# ProProject_MinSyBo_Star_2024-05-18.net
KiCad netlist of a schematic drawn in EasyEDA Pro
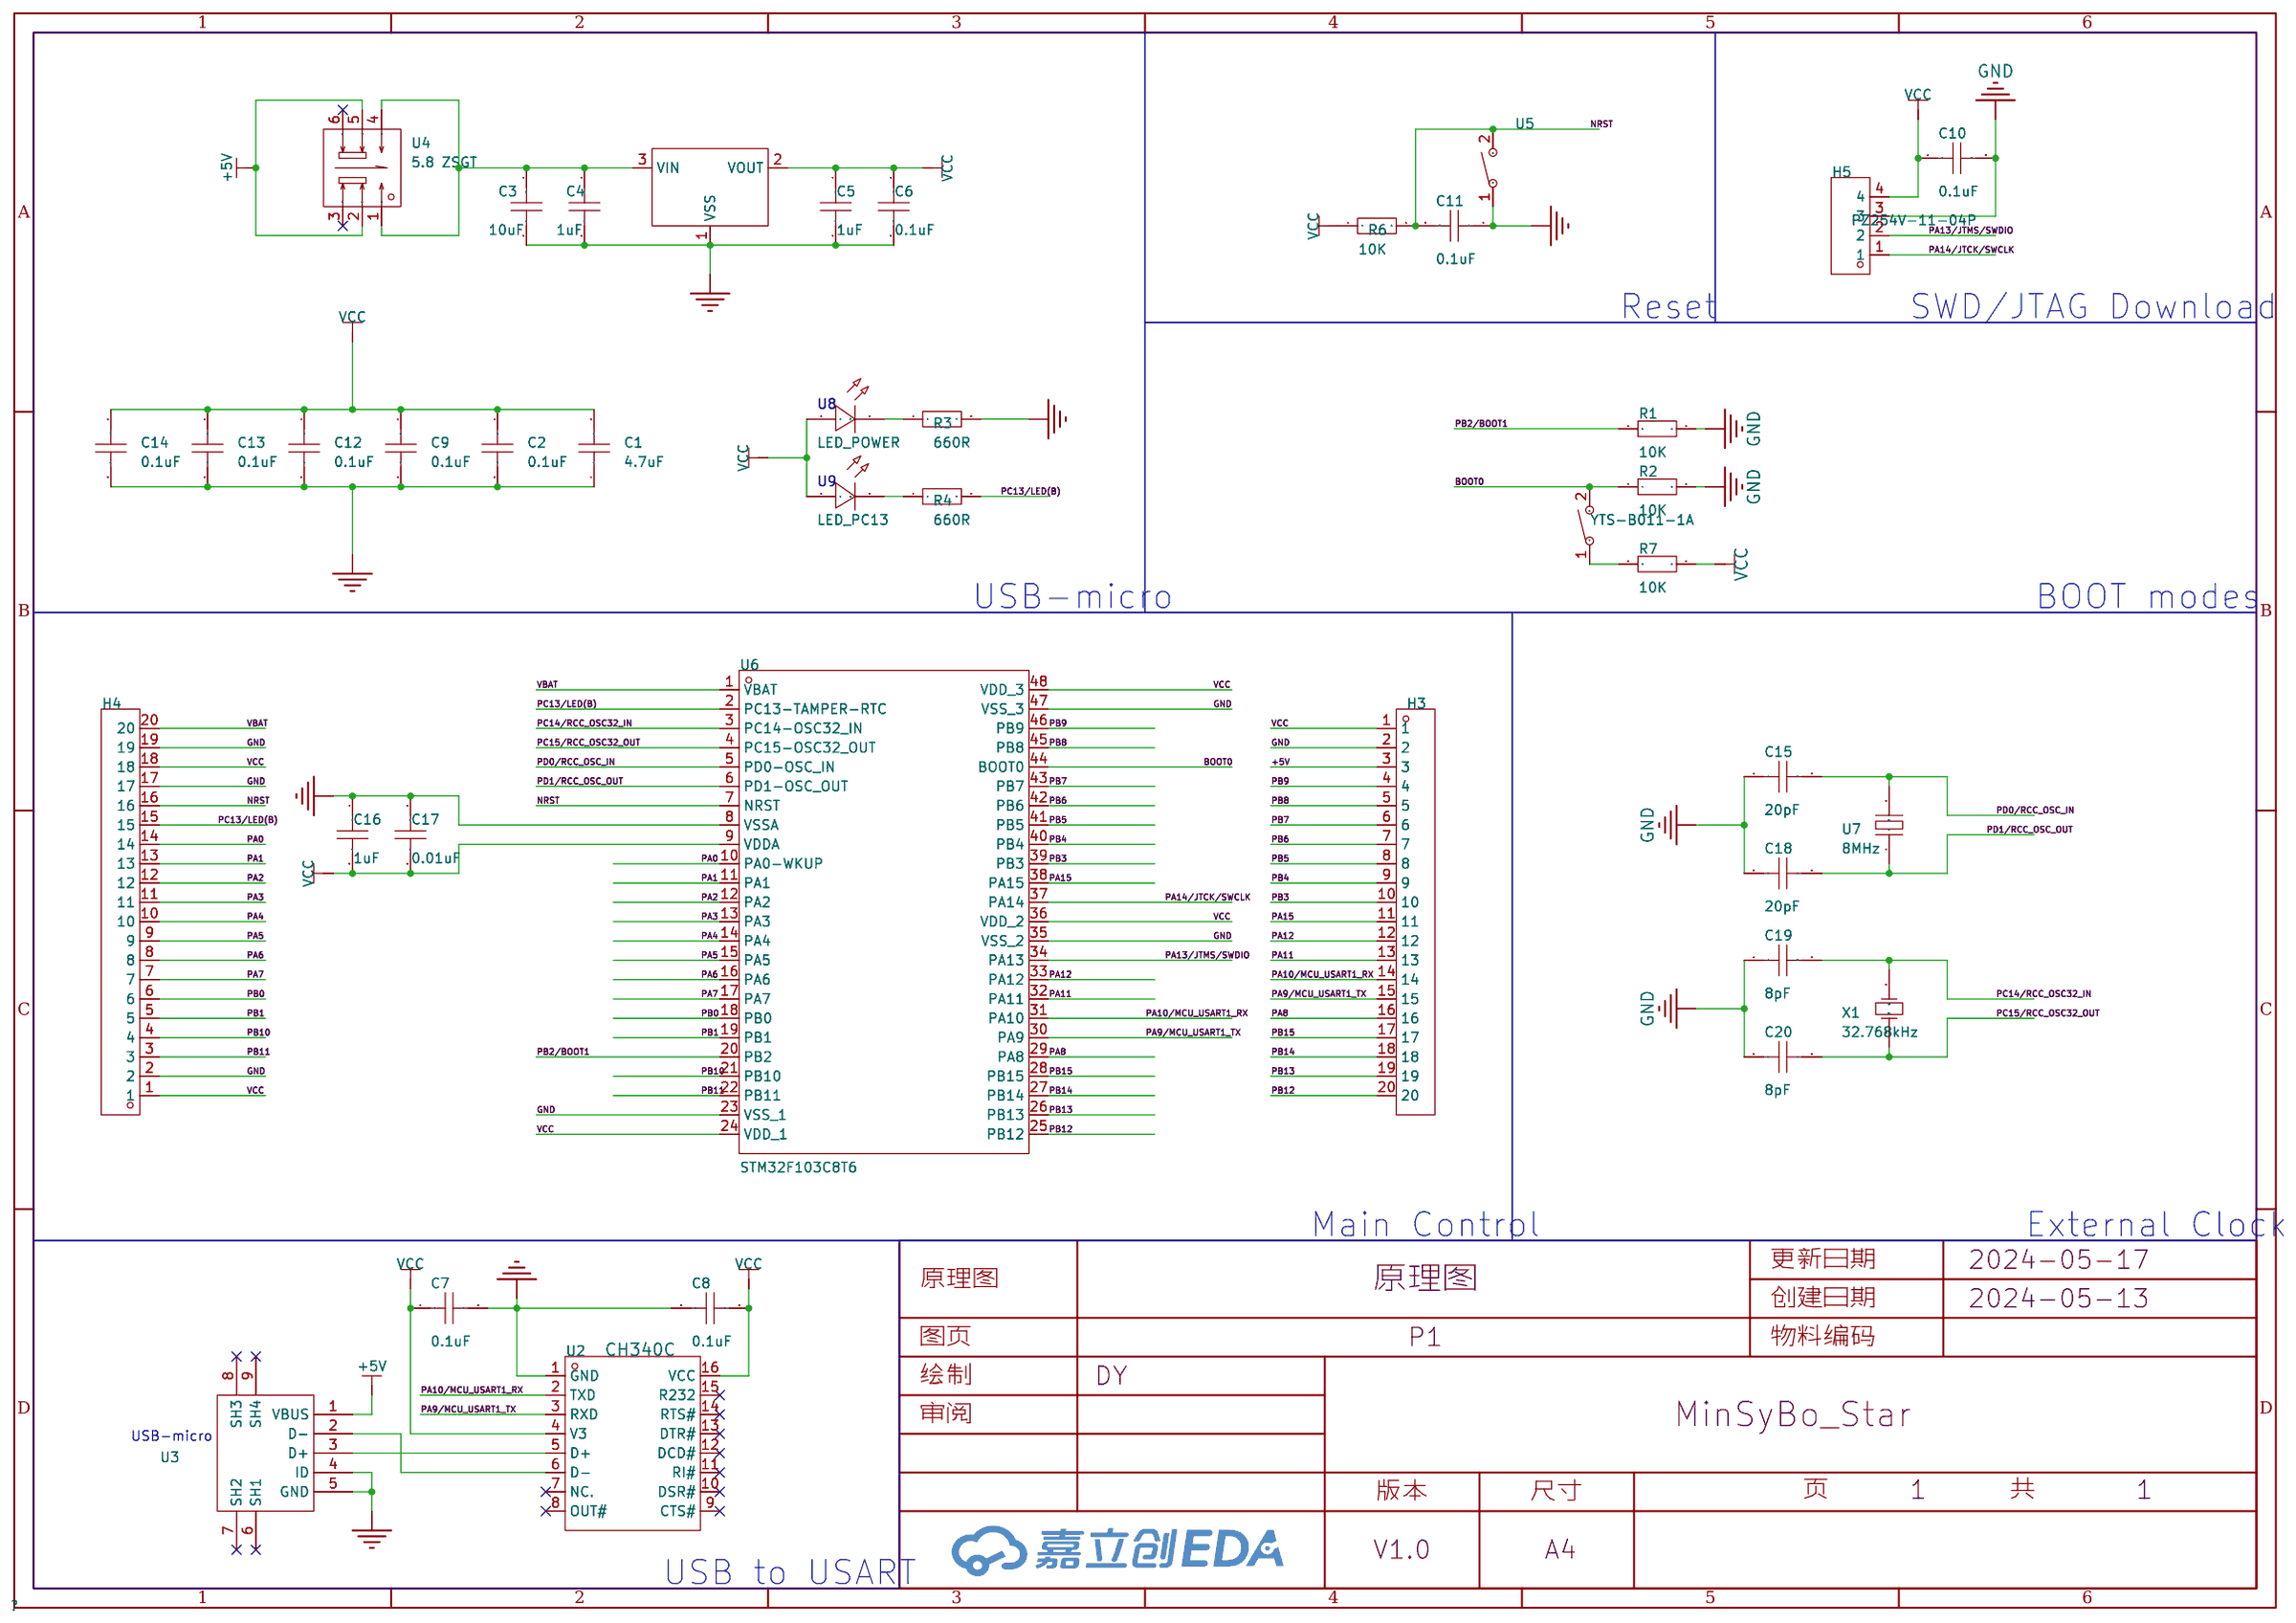
[diagram p0: schematic sheet]

(export (version "E")
  (design (tool "Eeschema 10.0.6"))
  (components
    (comp (ref "BOOT0")
      (value "YTS-B011-1A")
      (footprint "easyedapro:SW-TH_L6.1-W3.5-P6.60-LS8.0")
      (fields (field (name "Manufacturer") "YIYUAN(怡远)"))
      (libsource (lib "easyedapro") (part "YTS-B011-1A"))
    )
    (comp (ref "C1")
      (value "4.7uF")
      (footprint "easyedapro:C0603")
      (libsource (lib "easyedapro") (part "CapAcitance"))
    )
    (comp (ref "C2")
      (value "100nF")
      (footprint "easyedapro:C0603")
      (libsource (lib "easyedapro") (part "CapAcitance"))
    )
    (comp (ref "C3")
      (value "10uF")
      (footprint "easyedapro:C0603")
      (fields
        (field (name "Manufacturer Part") "CL10A106KP8NNNC")
        (field (name "Manufacturer") "SAMSUNG(三星)")
        (field (name "Tolerance") "±10%")
      )
      (libsource (lib "easyedapro") (part "CapAcitance"))
    )
    (comp (ref "C4")
      (value "1uF")
      (footprint "easyedapro:C0603")
      (libsource (lib "easyedapro") (part "CapAcitance"))
    )
    (comp (ref "C5")
      (value "1uF")
      (footprint "easyedapro:C0603")
      (libsource (lib "easyedapro") (part "CapAcitance"))
    )
    (comp (ref "C6")
      (value "0.1uF")
      (footprint "easyedapro:C0603")
      (libsource (lib "easyedapro") (part "CapAcitance"))
    )
    (comp (ref "C7")
      (value "0.1uF")
      (footprint "easyedapro:C0603")
      (libsource (lib "easyedapro") (part "CapAcitance"))
    )
    (comp (ref "C8")
      (value "0.1uF")
      (footprint "easyedapro:C0603")
      (libsource (lib "easyedapro") (part "CapAcitance"))
    )
    (comp (ref "C9")
      (value "100nF")
      (footprint "easyedapro:C0603")
      (libsource (lib "easyedapro") (part "CapAcitance"))
    )
    (comp (ref "C10")
      (value "0.1uF")
      (footprint "easyedapro:C0603")
      (libsource (lib "easyedapro") (part "CapAcitance"))
    )
    (comp (ref "C11")
      (value "0.1uF")
      (footprint "easyedapro:C0603")
      (libsource (lib "easyedapro") (part "CapAcitance"))
    )
    (comp (ref "C12")
      (value "100nF")
      (footprint "easyedapro:C0603")
      (libsource (lib "easyedapro") (part "CapAcitance"))
    )
    (comp (ref "C13")
      (value "100nF")
      (footprint "easyedapro:C0603")
      (libsource (lib "easyedapro") (part "CapAcitance"))
    )
    (comp (ref "C14")
      (value "100nF")
      (footprint "easyedapro:C0603")
      (libsource (lib "easyedapro") (part "CapAcitance"))
    )
    (comp (ref "C15")
      (value "20pF")
      (footprint "easyedapro:C0603")
      (libsource (lib "easyedapro") (part "CapAcitance"))
    )
    (comp (ref "C16")
      (value "1uF")
      (footprint "easyedapro:C0603")
      (libsource (lib "easyedapro") (part "CapAcitance"))
    )
    (comp (ref "C17")
      (value "0.01uF")
      (footprint "easyedapro:C0603")
      (libsource (lib "easyedapro") (part "CapAcitance"))
    )
    (comp (ref "C18")
      (value "20pF")
      (footprint "easyedapro:C0603")
      (libsource (lib "easyedapro") (part "CapAcitance"))
    )
    (comp (ref "C19")
      (value "8pF")
      (footprint "easyedapro:C0603")
      (libsource (lib "easyedapro") (part "CapAcitance"))
    )
    (comp (ref "C20")
      (value "8pF")
      (footprint "easyedapro:C0603")
      (libsource (lib "easyedapro") (part "CapAcitance"))
    )
    (comp (ref "H3")
      (value "2.54-1*20P直针")
      (footprint "easyedapro:HDR-TH_20P-P2.54-V-M-1")
      (fields (field (name "Manufacturer") "BOOMELE(博穆精密)"))
      (libsource (lib "easyedapro") (part "HDR_2.54-1x20P"))
    )
    (comp (ref "H4")
      (value "2.54-1*20P直针")
      (footprint "easyedapro:HDR-TH_20P-P2.54-V-M-1")
      (fields (field (name "Manufacturer") "BOOMELE(博穆精密)"))
      (libsource (lib "easyedapro") (part "HDR_2.54-1x20P"))
    )
    (comp (ref "H5")
      (value "PZ254V-11-04P")
      (footprint "easyedapro:HDR-TH_4P-P2.54-V-M")
      (fields (field (name "Manufacturer") "XFCN(兴飞)"))
      (libsource (lib "easyedapro") (part "PZ254V-11-04P"))
    )
    (comp (ref "R1") (value "10K") (footprint "easyedapro:R0603") (libsource (lib "easyedapro") (part "电阻")))
    (comp (ref "R2") (value "10K") (footprint "easyedapro:R0603") (libsource (lib "easyedapro") (part "电阻")))
    (comp (ref "R3") (value "660R") (footprint "easyedapro:R0603") (libsource (lib "easyedapro") (part "电阻")))
    (comp (ref "R4") (value "660R") (footprint "easyedapro:R0603") (libsource (lib "easyedapro") (part "电阻")))
    (comp (ref "R6") (value "10K") (footprint "easyedapro:R0603") (libsource (lib "easyedapro") (part "电阻")))
    (comp (ref "R7") (value "10K") (footprint "easyedapro:R0603") (libsource (lib "easyedapro") (part "电阻")))
    (comp (ref "U1")
      (value "XC6206P332MR")
      (footprint "easyedapro:SOT-23-3_L2.9-W1.3-P1.90-LS2.4-BR")
      (description "输出类型:固定;最大输入电压:8V;输出电压:3.3V;最大输出电流:300mA;输出极性:正极;")
      (fields (field (name "Manufacturer") "HXY MOSFET(华轩阳电子)"))
      (libsource (lib "easyedapro") (part "XC6206P332MR_C5148692"))
    )
    (comp (ref "U2")
      (value "CH340C")
      (footprint "easyedapro:SOP-16_L10.0-W3.9-P1.27-LS6.0-BL")
      (description "应用功能:收发器;接口协议:USB 2.0;数据速率:2Mbps;")
      (fields (field (name "Manufacturer") "WCH(南京沁恒)"))
      (libsource (lib "easyedapro") (part "CH340C"))
    )
    (comp (ref "U3")
      (value "MicroXNJ")
      (footprint "easyedapro:MICRO-USB-SMD_MICROXNJ")
      (description "连接器类型:Micro-B;标准:USB 2.0;公母:母;端口数量:1;触点数量:5P;安装方式:卧贴;额定电流 - 电源:1A;工作温度范围:-20°C~+85°C;")
      (fields (field (name "Manufacturer") "SHOU HAN(首韩)"))
      (libsource (lib "easyedapro") (part "MICROXNJ"))
    )
    (comp (ref "U4")
      (value "5.8 ZSGT")
      (footprint "easyedapro:SW-TH_5.8ZSGT")
      (description "电路结构:双刀双掷;自锁/无锁:自锁;安装方式:直插;触点电流:110mA;额定电压 (DC):30V;带灯:不带;作用力:150gf;机械寿命:10万次;")
      (fields (field (name "Manufacturer") "SHOU HAN(首韩)"))
      (libsource (lib "easyedapro") (part "5.8 ZSGT"))
    )
    (comp (ref "U5")
      (value "YTS-B011-1A")
      (footprint "easyedapro:SW-TH_L6.1-W3.5-P6.60-LS8.0")
      (fields (field (name "Manufacturer") "YIYUAN(怡远)"))
      (libsource (lib "easyedapro") (part "YTS-B011-1A"))
    )
    (comp (ref "U6")
      (value "STM32F103C8T6")
      (footprint "easyedapro:LQFP-48_L7.0-W7.0-P0.50-LS9.0-BL")
      (description "CPU内核:ARM-M3;程序存储容量:64KB;RAM总容量:20KB;GPIO端口数量:37;工作电压范围:2V~3.6V;CPU最大主频:72MHz;程序存储器类型:FLASH;")
      (fields (field (name "Manufacturer") "ST(意法半导体)"))
      (libsource (lib "easyedapro") (part "STM32F103C8T6"))
    )
    (comp (ref "U7")
      (value "8MHz")
      (footprint "easyedapro:HC-49SMD_L11.1-W4.8")
      (description "晶振类型:贴片晶振;频率:8MHz;常温频差:±10ppm;外接负载电容:20pF;频率稳定度(全温):±30ppm;")
      (fields (field (name "Manufacturer Part") "RC08000619") (field (name "Manufacturer") "TROQ(创捷)"))
      (libsource (lib "easyedapro") (part "RC08000619"))
    )
    (comp (ref "U8")
      (value "LED_POWER")
      (footprint "easyedapro:LED_0603")
      (libsource (lib "easyedapro") (part "LED_G"))
    )
    (comp (ref "U9")
      (value "LED_PC13")
      (footprint "easyedapro:LED_0603")
      (libsource (lib "easyedapro") (part "LED_B"))
    )
    (comp (ref "X1")
      (value "32.768kHz")
      (footprint "easyedapro:OSC-TH_BD3.8-P0.50")
      (description "晶振类型:直插晶振;频率:32.768kHz;常温频差:±20ppm;外接负载电容:12.5pF;频率稳定度(全温):±20ppm;")
      (fields (field (name "Manufacturer Part") "K383276812520") (field (name "Manufacturer") "KYX(凯越翔)"))
      (libsource (lib "easyedapro") (part "K383276812520"))
    )
  )
  (nets
    (net (code "1") (name "+5V") (class "Default")
      (node (ref "H3") (pin "3") (pinfunction "3_3") (pintype "input"))
      (node (ref "U3") (pin "1") (pinfunction "VBUS_1") (pintype "unspecified"))
      (node (ref "U4") (pin "2") (pinfunction "2_2") (pintype "unspecified"))
      (node (ref "U4") (pin "5") (pinfunction "5_5") (pintype "unspecified"))
    )
    (net (code "2") (name "/BOOT0") (class "Default")
      (node (ref "BOOT0") (pin "2") (pinfunction "2_2") (pintype "unspecified"))
      (node (ref "R2") (pin "1") (pinfunction "1_1") (pintype "input"))
      (node (ref "U6") (pin "44") (pinfunction "BOOT0_44") (pintype "unspecified"))
    )
    (net (code "3") (name "/NRST") (class "Default")
      (node (ref "C11") (pin "2") (pinfunction "2_2") (pintype "input"))
      (node (ref "H4") (pin "16") (pinfunction "16_16") (pintype "input"))
      (node (ref "R6") (pin "2") (pinfunction "2_2") (pintype "input"))
      (node (ref "U5") (pin "2") (pinfunction "2_2") (pintype "unspecified"))
      (node (ref "U6") (pin "7") (pinfunction "NRST_7") (pintype "unspecified"))
    )
    (net (code "4") (name "/PA0") (class "Default")
      (node (ref "H4") (pin "14") (pinfunction "14_14") (pintype "input"))
      (node (ref "U6") (pin "10") (pinfunction "PA0-WKUP_10") (pintype "unspecified"))
    )
    (net (code "5") (name "/PA1") (class "Default")
      (node (ref "H4") (pin "13") (pinfunction "13_13") (pintype "input"))
      (node (ref "U6") (pin "11") (pinfunction "PA1_11") (pintype "unspecified"))
    )
    (net (code "6") (name "/PA2") (class "Default")
      (node (ref "H4") (pin "12") (pinfunction "12_12") (pintype "input"))
      (node (ref "U6") (pin "12") (pinfunction "PA2_12") (pintype "unspecified"))
    )
    (net (code "7") (name "/PA3") (class "Default")
      (node (ref "H4") (pin "11") (pinfunction "11_11") (pintype "input"))
      (node (ref "U6") (pin "13") (pinfunction "PA3_13") (pintype "unspecified"))
    )
    (net (code "8") (name "/PA4") (class "Default")
      (node (ref "H4") (pin "10") (pinfunction "10_10") (pintype "input"))
      (node (ref "U6") (pin "14") (pinfunction "PA4_14") (pintype "unspecified"))
    )
    (net (code "9") (name "/PA5") (class "Default")
      (node (ref "H4") (pin "9") (pinfunction "9_9") (pintype "input"))
      (node (ref "U6") (pin "15") (pinfunction "PA5_15") (pintype "unspecified"))
    )
    (net (code "10") (name "/PA6") (class "Default")
      (node (ref "H4") (pin "8") (pinfunction "8_8") (pintype "input"))
      (node (ref "U6") (pin "16") (pinfunction "PA6_16") (pintype "unspecified"))
    )
    (net (code "11") (name "/PA7") (class "Default")
      (node (ref "H4") (pin "7") (pinfunction "7_7") (pintype "input"))
      (node (ref "U6") (pin "17") (pinfunction "PA7_17") (pintype "unspecified"))
    )
    (net (code "12") (name "/PA8") (class "Default")
      (node (ref "H3") (pin "16") (pinfunction "16_16") (pintype "input"))
      (node (ref "U6") (pin "29") (pinfunction "PA8_29") (pintype "unspecified"))
    )
    (net (code "13") (name "/PA9{slash}MCU_USART1_TX") (class "Default")
      (node (ref "H3") (pin "15") (pinfunction "15_15") (pintype "input"))
      (node (ref "U2") (pin "3") (pinfunction "RXD_3") (pintype "unspecified"))
      (node (ref "U6") (pin "30") (pinfunction "PA9_30") (pintype "unspecified"))
    )
    (net (code "14") (name "/PA10{slash}MCU_USART1_RX") (class "Default")
      (node (ref "H3") (pin "14") (pinfunction "14_14") (pintype "input"))
      (node (ref "U2") (pin "2") (pinfunction "TXD_2") (pintype "unspecified"))
      (node (ref "U6") (pin "31") (pinfunction "PA10_31") (pintype "unspecified"))
    )
    (net (code "15") (name "/PA11") (class "Default")
      (node (ref "H3") (pin "13") (pinfunction "13_13") (pintype "input"))
      (node (ref "U6") (pin "32") (pinfunction "PA11_32") (pintype "unspecified"))
    )
    (net (code "16") (name "/PA12") (class "Default")
      (node (ref "H3") (pin "12") (pinfunction "12_12") (pintype "input"))
      (node (ref "U6") (pin "33") (pinfunction "PA12_33") (pintype "unspecified"))
    )
    (net (code "17") (name "/PA13{slash}JTMS{slash}SWDIO") (class "Default")
      (node (ref "H5") (pin "2") (pinfunction "2_2") (pintype "unspecified"))
      (node (ref "U6") (pin "34") (pinfunction "PA13_34") (pintype "unspecified"))
    )
    (net (code "18") (name "/PA14{slash}JTCK{slash}SWCLK") (class "Default")
      (node (ref "H5") (pin "1") (pinfunction "1_1") (pintype "unspecified"))
      (node (ref "U6") (pin "37") (pinfunction "PA14_37") (pintype "unspecified"))
    )
    (net (code "19") (name "/PA15") (class "Default")
      (node (ref "H3") (pin "11") (pinfunction "11_11") (pintype "input"))
      (node (ref "U6") (pin "38") (pinfunction "PA15_38") (pintype "unspecified"))
    )
    (net (code "20") (name "/PB0") (class "Default")
      (node (ref "H4") (pin "6") (pinfunction "6_6") (pintype "input"))
      (node (ref "U6") (pin "18") (pinfunction "PB0_18") (pintype "unspecified"))
    )
    (net (code "21") (name "/PB1") (class "Default")
      (node (ref "H4") (pin "5") (pinfunction "5_5") (pintype "input"))
      (node (ref "U6") (pin "19") (pinfunction "PB1_19") (pintype "unspecified"))
    )
    (net (code "22") (name "/PB2{slash}BOOT1") (class "Default")
      (node (ref "R1") (pin "2") (pinfunction "2_2") (pintype "input"))
      (node (ref "U6") (pin "20") (pinfunction "PB2_20") (pintype "unspecified"))
    )
    (net (code "23") (name "/PB3") (class "Default")
      (node (ref "H3") (pin "10") (pinfunction "10_10") (pintype "input"))
      (node (ref "U6") (pin "39") (pinfunction "PB3_39") (pintype "unspecified"))
    )
    (net (code "24") (name "/PB4") (class "Default")
      (node (ref "H3") (pin "9") (pinfunction "9_9") (pintype "input"))
      (node (ref "U6") (pin "40") (pinfunction "PB4_40") (pintype "unspecified"))
    )
    (net (code "25") (name "/PB5") (class "Default")
      (node (ref "H3") (pin "8") (pinfunction "8_8") (pintype "input"))
      (node (ref "U6") (pin "41") (pinfunction "PB5_41") (pintype "unspecified"))
    )
    (net (code "26") (name "/PB6") (class "Default")
      (node (ref "H3") (pin "7") (pinfunction "7_7") (pintype "input"))
      (node (ref "U6") (pin "42") (pinfunction "PB6_42") (pintype "unspecified"))
    )
    (net (code "27") (name "/PB7") (class "Default")
      (node (ref "H3") (pin "6") (pinfunction "6_6") (pintype "input"))
      (node (ref "U6") (pin "43") (pinfunction "PB7_43") (pintype "unspecified"))
    )
    (net (code "28") (name "/PB8") (class "Default")
      (node (ref "H3") (pin "5") (pinfunction "5_5") (pintype "input"))
      (node (ref "U6") (pin "45") (pinfunction "PB8_45") (pintype "unspecified"))
    )
    (net (code "29") (name "/PB9") (class "Default")
      (node (ref "H3") (pin "4") (pinfunction "4_4") (pintype "input"))
      (node (ref "U6") (pin "46") (pinfunction "PB9_46") (pintype "unspecified"))
    )
    (net (code "30") (name "/PB10") (class "Default")
      (node (ref "H4") (pin "4") (pinfunction "4_4") (pintype "input"))
      (node (ref "U6") (pin "21") (pinfunction "PB10_21") (pintype "unspecified"))
    )
    (net (code "31") (name "/PB11") (class "Default")
      (node (ref "H4") (pin "3") (pinfunction "3_3") (pintype "input"))
      (node (ref "U6") (pin "22") (pinfunction "PB11_22") (pintype "unspecified"))
    )
    (net (code "32") (name "/PB12") (class "Default")
      (node (ref "H3") (pin "20") (pinfunction "20_20") (pintype "input"))
      (node (ref "U6") (pin "25") (pinfunction "PB12_25") (pintype "unspecified"))
    )
    (net (code "33") (name "/PB13") (class "Default")
      (node (ref "H3") (pin "19") (pinfunction "19_19") (pintype "input"))
      (node (ref "U6") (pin "26") (pinfunction "PB13_26") (pintype "unspecified"))
    )
    (net (code "34") (name "/PB14") (class "Default")
      (node (ref "H3") (pin "18") (pinfunction "18_18") (pintype "input"))
      (node (ref "U6") (pin "27") (pinfunction "PB14_27") (pintype "unspecified"))
    )
    (net (code "35") (name "/PB15") (class "Default")
      (node (ref "H3") (pin "17") (pinfunction "17_17") (pintype "input"))
      (node (ref "U6") (pin "28") (pinfunction "PB15_28") (pintype "unspecified"))
    )
    (net (code "36") (name "/PC13{slash}LED(B)") (class "Default")
      (node (ref "H4") (pin "15") (pinfunction "15_15") (pintype "input"))
      (node (ref "R4") (pin "2") (pinfunction "2_2") (pintype "input"))
      (node (ref "U6") (pin "2") (pinfunction "PC13-TAMPER-RTC_2") (pintype "unspecified"))
    )
    (net (code "37") (name "/PC14{slash}RCC_OSC32_IN") (class "Default")
      (node (ref "C19") (pin "2") (pinfunction "2_2") (pintype "input"))
      (node (ref "U6") (pin "3") (pinfunction "PC14-OSC32_IN_3") (pintype "unspecified"))
      (node (ref "X1") (pin "2") (pinfunction "OSC2_2") (pintype "unspecified"))
    )
    (net (code "38") (name "/PC15{slash}RCC_OSC32_OUT") (class "Default")
      (node (ref "C20") (pin "2") (pinfunction "2_2") (pintype "input"))
      (node (ref "U6") (pin "4") (pinfunction "PC15-OSC32_OUT_4") (pintype "unspecified"))
      (node (ref "X1") (pin "1") (pinfunction "OSC1_1") (pintype "unspecified"))
    )
    (net (code "39") (name "/PD0{slash}RCC_OSC_IN") (class "Default")
      (node (ref "C15") (pin "2") (pinfunction "2_2") (pintype "input"))
      (node (ref "U6") (pin "5") (pinfunction "PD0-OSC_IN_5") (pintype "unspecified"))
      (node (ref "U7") (pin "2") (pinfunction "GND_2") (pintype "input"))
    )
    (net (code "40") (name "/PD1{slash}RCC_OSC_OUT") (class "Default")
      (node (ref "C18") (pin "2") (pinfunction "2_2") (pintype "input"))
      (node (ref "U6") (pin "6") (pinfunction "PD1-OSC_OUT_6") (pintype "unspecified"))
      (node (ref "U7") (pin "1") (pinfunction "1_1") (pintype "input"))
    )
    (net (code "41") (name "/VBAT") (class "Default")
      (node (ref "H4") (pin "20") (pinfunction "20_20") (pintype "input"))
      (node (ref "U6") (pin "1") (pinfunction "VBAT_1") (pintype "unspecified"))
    )
    (net (code "42") (name "GND") (class "Default")
      (node (ref "C1") (pin "1") (pinfunction "1_1") (pintype "input"))
      (node (ref "C10") (pin "2") (pinfunction "2_2") (pintype "input"))
      (node (ref "C11") (pin "1") (pinfunction "1_1") (pintype "input"))
      (node (ref "C12") (pin "2") (pinfunction "2_2") (pintype "input"))
      (node (ref "C13") (pin "2") (pinfunction "2_2") (pintype "input"))
      (node (ref "C14") (pin "2") (pinfunction "2_2") (pintype "input"))
      (node (ref "C15") (pin "1") (pinfunction "1_1") (pintype "input"))
      (node (ref "C16") (pin "1") (pinfunction "1_1") (pintype "input"))
      (node (ref "C17") (pin "1") (pinfunction "1_1") (pintype "input"))
      (node (ref "C18") (pin "1") (pinfunction "1_1") (pintype "input"))
      (node (ref "C19") (pin "1") (pinfunction "1_1") (pintype "input"))
      (node (ref "C2") (pin "2") (pinfunction "2_2") (pintype "input"))
      (node (ref "C20") (pin "1") (pinfunction "1_1") (pintype "input"))
      (node (ref "C3") (pin "2") (pinfunction "2_2") (pintype "input"))
      (node (ref "C4") (pin "2") (pinfunction "2_2") (pintype "input"))
      (node (ref "C5") (pin "2") (pinfunction "2_2") (pintype "input"))
      (node (ref "C6") (pin "2") (pinfunction "2_2") (pintype "input"))
      (node (ref "C7") (pin "2") (pinfunction "2_2") (pintype "input"))
      (node (ref "C8") (pin "1") (pinfunction "1_1") (pintype "input"))
      (node (ref "C9") (pin "2") (pinfunction "2_2") (pintype "input"))
      (node (ref "H3") (pin "2") (pinfunction "2_2") (pintype "input"))
      (node (ref "H4") (pin "17") (pinfunction "17_17") (pintype "input"))
      (node (ref "H4") (pin "19") (pinfunction "19_19") (pintype "input"))
      (node (ref "H4") (pin "2") (pinfunction "2_2") (pintype "input"))
      (node (ref "H5") (pin "3") (pinfunction "3_3") (pintype "unspecified"))
      (node (ref "R1") (pin "1") (pinfunction "1_1") (pintype "input"))
      (node (ref "R2") (pin "2") (pinfunction "2_2") (pintype "input"))
      (node (ref "R3") (pin "2") (pinfunction "2_2") (pintype "input"))
      (node (ref "U1") (pin "1") (pinfunction "VSS_1") (pintype "unspecified"))
      (node (ref "U2") (pin "1") (pinfunction "GND_1") (pintype "unspecified"))
      (node (ref "U3") (pin "4") (pinfunction "ID_4") (pintype "unspecified"))
      (node (ref "U3") (pin "5") (pinfunction "GND_5") (pintype "unspecified"))
      (node (ref "U5") (pin "1") (pinfunction "1_1") (pintype "unspecified"))
      (node (ref "U6") (pin "23") (pinfunction "VSS_1_23") (pintype "unspecified"))
      (node (ref "U6") (pin "35") (pinfunction "VSS_2_35") (pintype "unspecified"))
      (node (ref "U6") (pin "47") (pinfunction "VSS_3_47") (pintype "unspecified"))
      (node (ref "U6") (pin "8") (pinfunction "VSSA_8") (pintype "unspecified"))
    )
    (net (code "43") (name "Net-(BOOT0-Pad1)") (class "Default")
      (node (ref "BOOT0") (pin "1") (pinfunction "1_1") (pintype "unspecified"))
      (node (ref "R7") (pin "1") (pinfunction "1_1") (pintype "input"))
    )
    (net (code "44") (name "Net-(U1-VIN)") (class "Default")
      (node (ref "C3") (pin "1") (pinfunction "1_1") (pintype "input"))
      (node (ref "C4") (pin "1") (pinfunction "1_1") (pintype "input"))
      (node (ref "U1") (pin "3") (pinfunction "VIN_3") (pintype "unspecified"))
      (node (ref "U4") (pin "1") (pinfunction "1_1") (pintype "unspecified"))
      (node (ref "U4") (pin "4") (pinfunction "4_4") (pintype "unspecified"))
    )
    (net (code "45") (name "Net-(U2-D+)") (class "Default")
      (node (ref "U2") (pin "5") (pinfunction "D+_5") (pintype "unspecified"))
      (node (ref "U3") (pin "3") (pinfunction "D+_3") (pintype "unspecified"))
    )
    (net (code "46") (name "Net-(U2-D-)") (class "Default")
      (node (ref "U2") (pin "6") (pinfunction "D-_6") (pintype "unspecified"))
      (node (ref "U3") (pin "2") (pinfunction "D-_2") (pintype "unspecified"))
    )
    (net (code "47") (name "Net-(U8-C)") (class "Default")
      (node (ref "R3") (pin "1") (pinfunction "1_1") (pintype "input"))
      (node (ref "U8") (pin "1") (pinfunction "C_1") (pintype "input"))
    )
    (net (code "48") (name "Net-(U9-C)") (class "Default")
      (node (ref "R4") (pin "1") (pinfunction "1_1") (pintype "input"))
      (node (ref "U9") (pin "1") (pinfunction "C_1") (pintype "input"))
    )
    (net (code "49") (name "VCC") (class "Default")
      (node (ref "C1") (pin "2") (pinfunction "2_2") (pintype "input"))
      (node (ref "C10") (pin "1") (pinfunction "1_1") (pintype "input"))
      (node (ref "C12") (pin "1") (pinfunction "1_1") (pintype "input"))
      (node (ref "C13") (pin "1") (pinfunction "1_1") (pintype "input"))
      (node (ref "C14") (pin "1") (pinfunction "1_1") (pintype "input"))
      (node (ref "C16") (pin "2") (pinfunction "2_2") (pintype "input"))
      (node (ref "C17") (pin "2") (pinfunction "2_2") (pintype "input"))
      (node (ref "C2") (pin "1") (pinfunction "1_1") (pintype "input"))
      (node (ref "C5") (pin "1") (pinfunction "1_1") (pintype "input"))
      (node (ref "C6") (pin "1") (pinfunction "1_1") (pintype "input"))
      (node (ref "C7") (pin "1") (pinfunction "1_1") (pintype "input"))
      (node (ref "C8") (pin "2") (pinfunction "2_2") (pintype "input"))
      (node (ref "C9") (pin "1") (pinfunction "1_1") (pintype "input"))
      (node (ref "H3") (pin "1") (pinfunction "1_1") (pintype "input"))
      (node (ref "H4") (pin "1") (pinfunction "1_1") (pintype "input"))
      (node (ref "H4") (pin "18") (pinfunction "18_18") (pintype "input"))
      (node (ref "H5") (pin "4") (pinfunction "4_4") (pintype "unspecified"))
      (node (ref "R6") (pin "1") (pinfunction "1_1") (pintype "input"))
      (node (ref "R7") (pin "2") (pinfunction "2_2") (pintype "input"))
      (node (ref "U1") (pin "2") (pinfunction "VOUT_2") (pintype "unspecified"))
      (node (ref "U2") (pin "16") (pinfunction "VCC_16") (pintype "unspecified"))
      (node (ref "U2") (pin "4") (pinfunction "V3_4") (pintype "unspecified"))
      (node (ref "U6") (pin "24") (pinfunction "VDD_1_24") (pintype "unspecified"))
      (node (ref "U6") (pin "36") (pinfunction "VDD_2_36") (pintype "unspecified"))
      (node (ref "U6") (pin "48") (pinfunction "VDD_3_48") (pintype "unspecified"))
      (node (ref "U6") (pin "9") (pinfunction "VDDA_9") (pintype "unspecified"))
      (node (ref "U8") (pin "2") (pinfunction "A_2") (pintype "input"))
      (node (ref "U9") (pin "2") (pinfunction "A_2") (pintype "input"))
    )
    (net (code "50") (name "unconnected-(U2-CTS#-Pad9)") (class "Default")
      (node (ref "U2") (pin "9") (pinfunction "CTS#_9") (pintype "unspecified+no_connect"))
    )
    (net (code "51") (name "unconnected-(U2-DCD#-Pad12)") (class "Default")
      (node (ref "U2") (pin "12") (pinfunction "DCD#_12") (pintype "unspecified+no_connect"))
    )
    (net (code "52") (name "unconnected-(U2-DSR#-Pad10)") (class "Default")
      (node (ref "U2") (pin "10") (pinfunction "DSR#_10") (pintype "unspecified+no_connect"))
    )
    (net (code "53") (name "unconnected-(U2-DTR#-Pad13)") (class "Default")
      (node (ref "U2") (pin "13") (pinfunction "DTR#_13") (pintype "unspecified+no_connect"))
    )
    (net (code "54") (name "unconnected-(U2-NC.-Pad7)") (class "Default")
      (node (ref "U2") (pin "7") (pinfunction "NC._7") (pintype "unspecified+no_connect"))
    )
    (net (code "55") (name "unconnected-(U2-OUT#-Pad8)") (class "Default")
      (node (ref "U2") (pin "8") (pinfunction "OUT#_8") (pintype "unspecified+no_connect"))
    )
    (net (code "56") (name "unconnected-(U2-R232-Pad15)") (class "Default")
      (node (ref "U2") (pin "15") (pinfunction "R232_15") (pintype "unspecified+no_connect"))
    )
    (net (code "57") (name "unconnected-(U2-RI#-Pad11)") (class "Default")
      (node (ref "U2") (pin "11") (pinfunction "RI#_11") (pintype "unspecified+no_connect"))
    )
    (net (code "58") (name "unconnected-(U2-RTS#-Pad14)") (class "Default")
      (node (ref "U2") (pin "14") (pinfunction "RTS#_14") (pintype "unspecified+no_connect"))
    )
    (net (code "59") (name "unconnected-(U3-SH1-Pad6)") (class "Default")
      (node (ref "U3") (pin "6") (pinfunction "SH1_6") (pintype "unspecified+no_connect"))
    )
    (net (code "60") (name "unconnected-(U3-SH2-Pad7)") (class "Default")
      (node (ref "U3") (pin "7") (pinfunction "SH2_7") (pintype "unspecified+no_connect"))
    )
    (net (code "61") (name "unconnected-(U3-SH3-Pad8)") (class "Default")
      (node (ref "U3") (pin "8") (pinfunction "SH3_8") (pintype "unspecified+no_connect"))
    )
    (net (code "62") (name "unconnected-(U3-SH4-Pad9)") (class "Default")
      (node (ref "U3") (pin "9") (pinfunction "SH4_9") (pintype "unspecified+no_connect"))
    )
    (net (code "63") (name "unconnected-(U4-Pad3)") (class "Default")
      (node (ref "U4") (pin "3") (pinfunction "3_3") (pintype "unspecified+no_connect"))
    )
    (net (code "64") (name "unconnected-(U4-Pad6)") (class "Default")
      (node (ref "U4") (pin "6") (pinfunction "6_6") (pintype "unspecified+no_connect"))
    )
  )
)
